# 519_sch.net
KiCad netlist of a schematic drawn in EAGLE
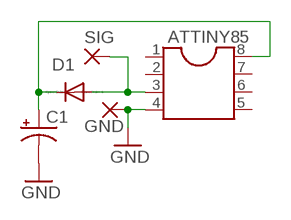
[diagram p0: schematic, sheet 1]

(export (version "E")
  (design (tool "Eeschema 10.0.6"))
  (components
    (comp (ref "ATTINY85")
      (value "DIL8")
      (footprint "eagle-import:DIL08")
      (libsource (lib "eagle-import") (part "DIL8"))
    )
    (comp (ref "C1")
      (value "CPOL-USE2,5-6E")
      (footprint "eagle-import:E2,5-6E")
      (libsource (lib "eagle-import") (part "CPOL-USE2,5-6E"))
    )
    (comp (ref "D1")
      (value "1N4148DO35-7")
      (footprint "eagle-import:DO35-7")
      (libsource (lib "eagle-import") (part "1N4148DO35-7"))
    )
    (comp (ref "GND")
      (value "3,81/1,4")
      (footprint "eagle-import:3,81_1,4")
      (libsource (lib "eagle-import") (part "3,81/1,4"))
    )
    (comp (ref "SIG")
      (value "3,81/1,4")
      (footprint "eagle-import:3,81_1,4")
      (libsource (lib "eagle-import") (part "3,81/1,4"))
    )
  )
  (nets
    (net (code "1") (name "GND") (class "Default")
      (node (ref "ATTINY85") (pin "4") (pinfunction "4_4") (pintype "passive"))
      (node (ref "C1") (pin "-") (pinfunction "-_-") (pintype "passive"))
      (node (ref "GND") (pin "1") (pinfunction "P_1") (pintype "passive"))
    )
    (net (code "2") (name "Net-(ATTINY85-Pad8)") (class "Default")
      (node (ref "ATTINY85") (pin "8") (pinfunction "8_8") (pintype "passive"))
      (node (ref "C1") (pin "+") (pinfunction "+_+") (pintype "passive"))
      (node (ref "D1") (pin "C") (pinfunction "C_C") (pintype "passive"))
    )
    (net (code "3") (name "Net-(SIG-P)") (class "Default")
      (node (ref "ATTINY85") (pin "3") (pinfunction "3_3") (pintype "passive"))
      (node (ref "D1") (pin "A") (pinfunction "A_A") (pintype "passive"))
      (node (ref "SIG") (pin "1") (pinfunction "P_1") (pintype "passive"))
    )
    (net (code "4") (name "unconnected-(ATTINY85-Pad1)") (class "Default")
      (node (ref "ATTINY85") (pin "1") (pinfunction "1_1") (pintype "passive"))
    )
    (net (code "5") (name "unconnected-(ATTINY85-Pad2)") (class "Default")
      (node (ref "ATTINY85") (pin "2") (pinfunction "2_2") (pintype "passive"))
    )
    (net (code "6") (name "unconnected-(ATTINY85-Pad5)") (class "Default")
      (node (ref "ATTINY85") (pin "5") (pinfunction "5_5") (pintype "passive"))
    )
    (net (code "7") (name "unconnected-(ATTINY85-Pad6)") (class "Default")
      (node (ref "ATTINY85") (pin "6") (pinfunction "6_6") (pintype "passive"))
    )
    (net (code "8") (name "unconnected-(ATTINY85-Pad7)") (class "Default")
      (node (ref "ATTINY85") (pin "7") (pinfunction "7_7") (pintype "passive"))
    )
  )
)
